# USBHeaders.net
KiCad netlist of a schematic drawn in Altium Designer
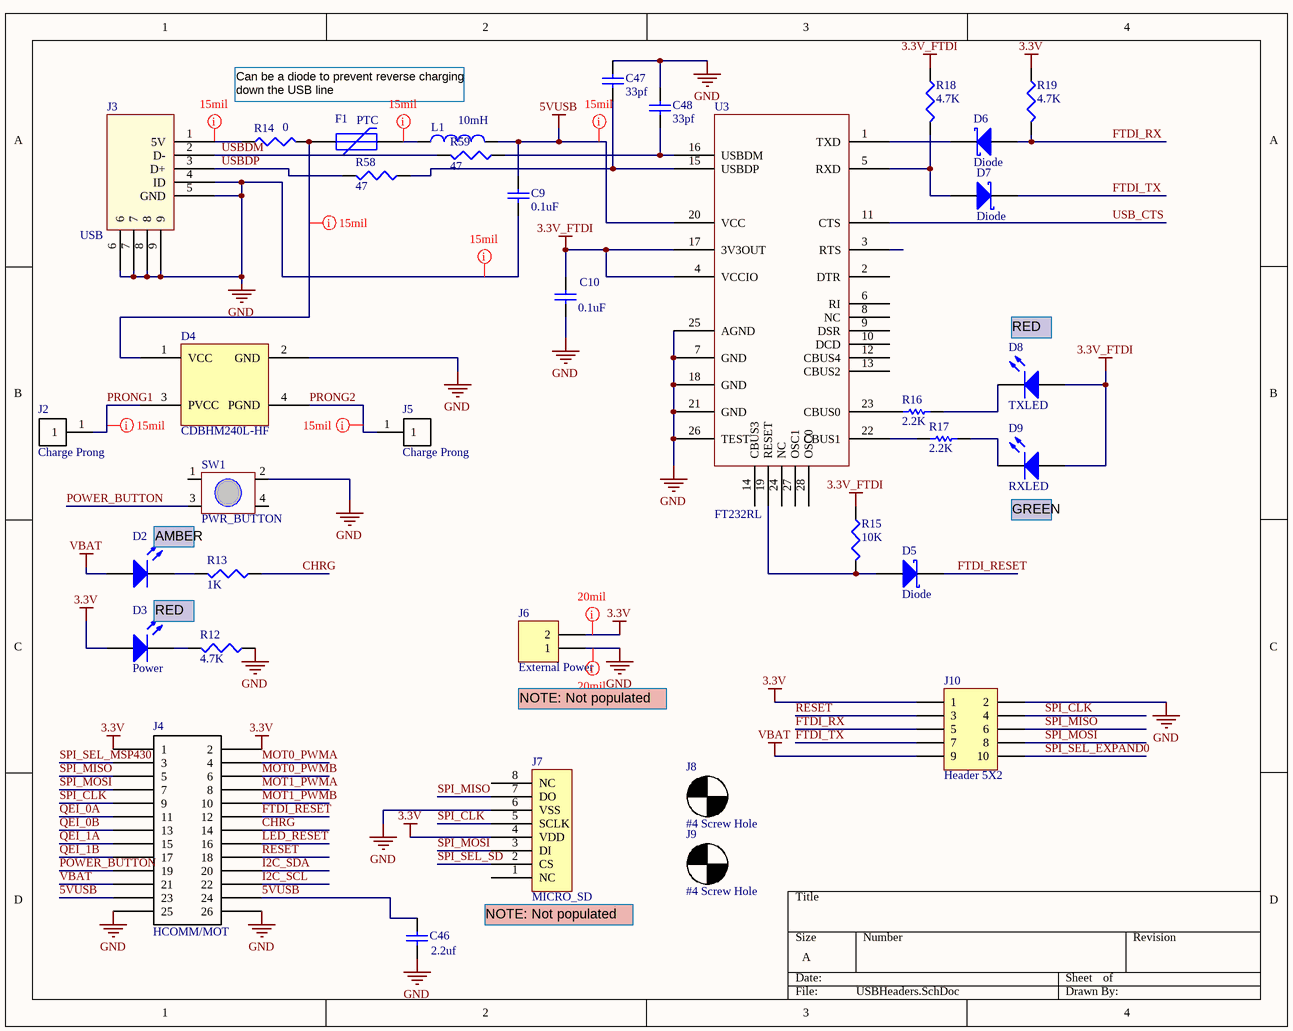
[diagram p0: USBHeaders.SchDoc]

(export (version "E")
  (design (tool "Eeschema 10.0.6"))
  (components
    (comp (ref "C9")
      (value "0.1uF")
      (footprint "CAPC1005L")
      (description "Capacitor")
      (fields
        (field (name "PART NUMBER") "C1005X5R1A104M050BA")
        (field (name "MANUFACTURER") "TDK")
        (field (name "PUBLISHER") "Altium Limited")
      )
      (libsource (lib "Miscellaneous Devices") (part "Cap"))
    )
    (comp (ref "C10")
      (value "0.1uF")
      (footprint "CAPC1005L")
      (description "Capacitor")
      (fields
        (field (name "PART NUMBER") "C1005X5R1A104M050BA")
        (field (name "MANUFACTURER") "TDK")
        (field (name "PUBLISHER") "Altium Limited")
      )
      (libsource (lib "Miscellaneous Devices") (part "Cap"))
    )
    (comp (ref "C46")
      (value "2.2uf")
      (footprint "J1-0603")
      (description "Capacitor (Semiconductor SIM Model)")
      (fields
        (field (name "PART NUMBER") "JMK107F225ZA-T")
        (field (name "MANUFACTURER") "Taiyo Yuden")
        (field (name "PUBLISHER") "Altium Limited")
      )
      (libsource (lib "Miscellaneous Devices") (part "Cap Semi"))
    )
    (comp (ref "C47")
      (value "33pf")
      (footprint "CAPC1005L")
      (description "Capacitor (Semiconductor SIM Model)")
      (fields
        (field (name "PART NUMBER") "GRM1555C1H330JA01D")
        (field (name "MANUFACTURER") "Murata")
        (field (name "PUBLISHER") "Altium Limited")
      )
      (libsource (lib "Miscellaneous Devices") (part "Cap Semi"))
    )
    (comp (ref "C48")
      (value "33pf")
      (footprint "CAPC1005L")
      (description "Capacitor (Semiconductor SIM Model)")
      (fields
        (field (name "PART NUMBER") "GRM1555C1H330JA01D")
        (field (name "MANUFACTURER") "Murata")
        (field (name "PUBLISHER") "Altium Limited")
      )
      (libsource (lib "Miscellaneous Devices") (part "Cap Semi"))
    )
    (comp (ref "D2")
      (value "Charge")
      (footprint "SurfaceMount(603)")
      (description "Typical RED, GREEN, YELLOW, AMBER GaAs LED")
      (fields
        (field (name "PART NUMBER") "LTST-C190AKT")
        (field (name "MANUFACTURER") "Lite-On")
        (field (name "PUBLISHER") "Altium Limited")
      )
      (libsource (lib "") (part "LED2_1"))
    )
    (comp (ref "D3")
      (value "Power")
      (footprint "SurfaceMount(603)")
      (fields (field (name "PART NUMBER") "LS Q976-NR-1") (field (name "MANUFACTURER") "Osram"))
      (libsource (lib "mrone") (part "LED"))
    )
    (comp (ref "D4")
      (value "CDBHM240L-HF")
      (footprint "DIODEARRAY_2AMPS")
      (fields
        (field (name "MPN") "CDBHM240L-HF")
        (field (name "PART NUMBER") "CDBHM240L - HF")
        (field (name "MANUFACTURER") "Comchip Technology")
      )
      (libsource (lib "mrone") (part "DiodeArray2Amps"))
    )
    (comp (ref "D5")
      (value "Diode")
      (footprint "SurfaceMount(603)")
      (fields (field (name "PART NUMBER") "CD0603-B00340") (field (name "MANUFACTURER") "Bourns"))
      (libsource (lib "mrone") (part "SchottkeyDiode"))
    )
    (comp (ref "D6")
      (value "Diode")
      (footprint "SurfaceMount(603)")
      (fields (field (name "PART NUMBER") "CD0603-B00340") (field (name "MANUFACTURER") "Bourns"))
      (libsource (lib "mrone") (part "SchottkeyDiode"))
    )
    (comp (ref "D7")
      (value "Diode")
      (footprint "SurfaceMount(603)")
      (fields (field (name "PART NUMBER") "CD0603-B00340") (field (name "MANUFACTURER") "Bourns"))
      (libsource (lib "mrone") (part "SchottkeyDiode"))
    )
    (comp (ref "D8")
      (value "TXLED")
      (footprint "SurfaceMount(603)")
      (description "Typical RED, GREEN, YELLOW, AMBER GaAs LED")
      (fields
        (field (name "PART NUMBER") "LS Q976-NR-1")
        (field (name "MANUFACTURER") "Osram")
        (field (name "PUBLISHER") "Altium Limited")
      )
      (libsource (lib "Miscellaneous Devices") (part "LED2"))
    )
    (comp (ref "D9")
      (value "RXLED")
      (footprint "SurfaceMount(603)")
      (description "Typical RED, GREEN, YELLOW, AMBER GaAs LED")
      (fields
        (field (name "PART NUMBER") "LTST-C191GKT")
        (field (name "MANUFACTURER") "Lite-On")
        (field (name "PUBLISHER") "Altium Limited")
      )
      (libsource (lib "Miscellaneous Devices") (part "LED2"))
    )
    (comp (ref "F1")
      (value "PTC")
      (footprint "ERJ8G-1206")
      (description "Fuse")
      (fields
        (field (name "PART NUMBER") "MF-NSMF200-2")
        (field (name "MANUFACTURER") "Bourns")
        (field (name "PUBLISHER") "Altium Limited")
      )
      (libsource (lib "mrone") (part "PTC_FUSE"))
    )
    (comp (ref "J2")
      (value "Charge Prong")
      (footprint "CHARGING_PRONG")
      (description "Charging Prong Hole with Plating")
      (libsource (lib "mrone") (part "CHARGE_PRONG"))
    )
    (comp (ref "J3")
      (value "USB")
      (footprint "USB Minib (thru-hole)")
      (fields (field (name "PART NUMBER") "51387-0578") (field (name "MANUFACTURER") "Molex"))
      (libsource (lib "mrone") (part "USB-ConnTH"))
    )
    (comp (ref "J4")
      (value "HCOMM/MOT")
      (footprint "HeaderSM 13x2")
      (description "Header, 2X20, 50mil, IDC")
      (fields (field (name "PART NUMBER") "SHF-113-01-L-D-SM-LC") (field (name "MANUFACTURER") "Samtec"))
      (libsource (lib "mrone") (part "HCOMM/HMOT"))
    )
    (comp (ref "J5")
      (value "Charge Prong")
      (footprint "CHARGING_PRONG")
      (description "Charging Prong Hole with Plating")
      (libsource (lib "mrone") (part "CHARGE_PRONG"))
    )
    (comp (ref "J6")
      (value "External Power")
      (footprint "HDR1X2")
      (description "Header, 2-Pin")
      (fields (field (name "PUBLISHER") "Altium Limited"))
      (libsource (lib "Miscellaneous Connectors") (part "Header 2"))
    )
    (comp (ref "J7")
      (value "MICRO_SD")
      (footprint "MICRO_SD")
      (fields (field (name "PART NUMBER") "101-00303-68") (field (name "MANUFACTURER") "Amphenol"))
      (libsource (lib "mrone") (part "MICRO_SD"))
    )
    (comp (ref "J8")
      (value "#4 Screw Hole")
      (footprint "#4_Screw_Hole")
      (description "A mechanical hole for mounting the board")
      (libsource (lib "mrone") (part "Mechanical_Hole"))
    )
    (comp (ref "J9")
      (value "#4 Screw Hole")
      (footprint "#4_Screw_Hole")
      (description "A mechanical hole for mounting the board")
      (libsource (lib "mrone") (part "Mechanical_Hole"))
    )
    (comp (ref "J10")
      (value "Header 5X2")
      (footprint "HDR2X5")
      (description "Header, 5-Pin, Dual row")
      (fields
        (field (name "PART NUMBER") "802-10-012-10-002101")
        (field (name "MANUFACTURER") "Preci-Dip")
        (field (name "PUBLISHER") "Altium Limited")
      )
      (libsource (lib "mrone") (part "Header 5X2"))
    )
    (comp (ref "L1")
      (value "10mH")
      (footprint "INDC2012L")
      (description "Inductor")
      (fields
        (field (name "PART NUMBER") "MMZ2012R102A")
        (field (name "MANUFACTURER") "TDK")
        (field (name "PUBLISHER") "Altium Limited")
      )
      (libsource (lib "Miscellaneous Devices") (part "Inductor"))
    )
    (comp (ref "R12")
      (value "4.7K")
      (footprint "RESC1608L")
      (description "Resistor")
      (fields
        (field (name "PART NUMBER") "CR0603-JW-472GLF")
        (field (name "MANUFACTURER") "Bourns")
        (field (name "PUBLISHER") "Altium Limited")
      )
      (libsource (lib "Miscellaneous Devices") (part "Res3"))
    )
    (comp (ref "R13")
      (value "1K")
      (footprint "RESC1608L")
      (description "Resistor")
      (fields
        (field (name "PART NUMBER") "SR03-1001")
        (field (name "MANUFACTURER") "Vishay")
        (field (name "PUBLISHER") "Altium Limited")
      )
      (libsource (lib "Miscellaneous Devices") (part "Res3"))
    )
    (comp (ref "R14")
      (value "0")
      (footprint "RESC1608L")
      (description "Resistor")
      (fields
        (field (name "PART NUMBER") "RMCF 1/16S 0 R")
        (field (name "MANUFACTURER") "Stackpole")
        (field (name "PUBLISHER") "Altium Limited")
      )
      (libsource (lib "Miscellaneous Devices") (part "Res3"))
    )
    (comp (ref "R15")
      (value "10K")
      (footprint "RESC1608L")
      (description "Resistor")
      (fields
        (field (name "PART NUMBER") "SR03-1002")
        (field (name "MANUFACTURER") "Vishay")
        (field (name "PUBLISHER") "Altium Limited")
      )
      (libsource (lib "Miscellaneous Devices") (part "Res3"))
    )
    (comp (ref "R16")
      (value "2.2K")
      (footprint "RESC1608L")
      (description "Resistor")
      (fields
        (field (name "PART NUMBER") "ERJ-3GEYJ-222V")
        (field (name "MANUFACTURER") "Panasonic")
        (field (name "PUBLISHER") "Altium Limited")
      )
      (libsource (lib "Miscellaneous Devices") (part "Res1"))
    )
    (comp (ref "R17")
      (value "2.2K")
      (footprint "RESC1608L")
      (description "Resistor")
      (fields
        (field (name "PART NUMBER") "ERJ-3GEYJ-222V")
        (field (name "MANUFACTURER") "Panasonic")
        (field (name "PUBLISHER") "Altium Limited")
      )
      (libsource (lib "Miscellaneous Devices") (part "Res1"))
    )
    (comp (ref "R18")
      (value "4.7K")
      (footprint "RESC1608L")
      (description "Resistor")
      (fields
        (field (name "PART NUMBER") "CR0603-JW-472GLF")
        (field (name "MANUFACTURER") "Bourns")
        (field (name "PUBLISHER") "Altium Limited")
      )
      (libsource (lib "Miscellaneous Devices") (part "Res3"))
    )
    (comp (ref "R19")
      (value "4.7K")
      (footprint "RESC1608L")
      (description "Resistor")
      (fields
        (field (name "PART NUMBER") "CR0603-JW-472GLF")
        (field (name "MANUFACTURER") "Bourns")
        (field (name "PUBLISHER") "Altium Limited")
      )
      (libsource (lib "Miscellaneous Devices") (part "Res3"))
    )
    (comp (ref "R58")
      (value "47")
      (footprint "RESC1608L")
      (description "Resistor")
      (fields
        (field (name "PART NUMBER") "ERJ-3GEYJ470V")
        (field (name "MANUFACTURER") "Panasonic")
        (field (name "PUBLISHER") "Altium Limited")
      )
      (libsource (lib "Miscellaneous Devices") (part "Res3"))
    )
    (comp (ref "R59")
      (value "47")
      (footprint "RESC1608L")
      (description "Resistor")
      (fields
        (field (name "PART NUMBER") "ERJ-3GEYJ470V")
        (field (name "MANUFACTURER") "Panasonic")
        (field (name "PUBLISHER") "Altium Limited")
      )
      (libsource (lib "Miscellaneous Devices") (part "Res3"))
    )
    (comp (ref "SW1")
      (value "PWR_BUTTON")
      (footprint "SwitchTall-TL330")
      (fields (field (name "PART NUMBER") "EVQ-P0N02B") (field (name "MANUFACTURER") "Panasonic"))
      (libsource (lib "mrone") (part "Switch-TL330"))
    )
    (comp (ref "U3")
      (value "FT232RL")
      (footprint "SSOP-28")
      (fields (field (name "MANUFACTURER") "FTDI"))
      (libsource (lib "mrone") (part "FT232RL"))
    )
  )
  (nets
    (net (code "2") (name "/CHRG") (class "Default")
      (node (ref "J4") (pin "14") (pinfunction "14_14") (pintype "passive"))
      (node (ref "R13") (pin "1") (pinfunction "1_1") (pintype "passive"))
    )
    (net (code "3") (name "/FTDI_RESET") (class "Default")
      (node (ref "D5") (pin "1") (pinfunction "K_1") (pintype "passive"))
      (node (ref "J4") (pin "12") (pinfunction "12_12") (pintype "passive"))
    )
    (net (code "4") (name "/FTDI_RX") (class "Default")
      (node (ref "D6") (pin "2") (pinfunction "A_2") (pintype "passive"))
      (node (ref "J10") (pin "5") (pinfunction "5_5") (pintype "passive"))
      (node (ref "R19") (pin "2") (pinfunction "2_2") (pintype "passive"))
    )
    (net (code "5") (name "/FTDI_TX") (class "Default")
      (node (ref "D7") (pin "1") (pinfunction "K_1") (pintype "passive"))
      (node (ref "J10") (pin "7") (pinfunction "7_7") (pintype "passive"))
    )
    (net (code "6") (name "/I2C_SCL") (class "Default")
      (node (ref "J4") (pin "22") (pinfunction "22_22") (pintype "passive"))
    )
    (net (code "7") (name "/I2C_SDA") (class "Default")
      (node (ref "J4") (pin "20") (pinfunction "20_20") (pintype "passive"))
    )
    (net (code "8") (name "/LED_RESET") (class "Default")
      (node (ref "J4") (pin "16") (pinfunction "16_16") (pintype "passive"))
    )
    (net (code "9") (name "/MOT0_PWMA") (class "Default")
      (node (ref "J4") (pin "4") (pinfunction "4_4") (pintype "passive"))
    )
    (net (code "10") (name "/MOT0_PWMB") (class "Default")
      (node (ref "J4") (pin "6") (pinfunction "6_6") (pintype "passive"))
    )
    (net (code "11") (name "/MOT1_PWMA") (class "Default")
      (node (ref "J4") (pin "8") (pinfunction "8_8") (pintype "passive"))
    )
    (net (code "12") (name "/MOT1_PWMB") (class "Default")
      (node (ref "J4") (pin "10") (pinfunction "10_10") (pintype "passive"))
    )
    (net (code "13") (name "/POWER_BUTTON") (class "Default")
      (node (ref "J4") (pin "19") (pinfunction "19_19") (pintype "passive"))
      (node (ref "SW1") (pin "3") (pinfunction "3_3") (pintype "passive"))
    )
    (net (code "14") (name "/PRONG1") (class "Default")
      (node (ref "D4") (pin "3") (pinfunction "PVCC_3") (pintype "passive"))
      (node (ref "J2") (pin "1") (pinfunction "1_1") (pintype "passive"))
    )
    (net (code "15") (name "/PRONG2") (class "Default")
      (node (ref "D4") (pin "4") (pinfunction "PGND_4") (pintype "passive"))
      (node (ref "J5") (pin "1") (pinfunction "1_1") (pintype "passive"))
    )
    (net (code "16") (name "/QEI_0A") (class "Default")
      (node (ref "J4") (pin "11") (pinfunction "11_11") (pintype "passive"))
    )
    (net (code "17") (name "/QEI_0B") (class "Default")
      (node (ref "J4") (pin "13") (pinfunction "13_13") (pintype "passive"))
    )
    (net (code "18") (name "/QEI_1A") (class "Default")
      (node (ref "J4") (pin "15") (pinfunction "15_15") (pintype "passive"))
    )
    (net (code "19") (name "/QEI_1B") (class "Default")
      (node (ref "J4") (pin "17") (pinfunction "17_17") (pintype "passive"))
    )
    (net (code "20") (name "/RESET") (class "Default")
      (node (ref "J10") (pin "3") (pinfunction "3_3") (pintype "passive"))
      (node (ref "J4") (pin "18") (pinfunction "18_18") (pintype "passive"))
    )
    (net (code "21") (name "/SPI_CLK") (class "Default")
      (node (ref "J10") (pin "4") (pinfunction "4_4") (pintype "passive"))
      (node (ref "J4") (pin "9") (pinfunction "9_9") (pintype "passive"))
      (node (ref "J7") (pin "5") (pinfunction "SCLK_5") (pintype "passive"))
    )
    (net (code "22") (name "/SPI_MISO") (class "Default")
      (node (ref "J10") (pin "6") (pinfunction "6_6") (pintype "passive"))
      (node (ref "J4") (pin "5") (pinfunction "5_5") (pintype "passive"))
      (node (ref "J7") (pin "7") (pinfunction "DO_7") (pintype "passive"))
    )
    (net (code "23") (name "/SPI_MOSI") (class "Default")
      (node (ref "J10") (pin "8") (pinfunction "8_8") (pintype "passive"))
      (node (ref "J4") (pin "7") (pinfunction "7_7") (pintype "passive"))
      (node (ref "J7") (pin "3") (pinfunction "DI_3") (pintype "passive"))
    )
    (net (code "24") (name "/SPI_SEL_EXPAND0") (class "Default")
      (node (ref "J10") (pin "10") (pinfunction "10_10") (pintype "passive"))
    )
    (net (code "25") (name "/SPI_SEL_MSP430") (class "Default")
      (node (ref "J4") (pin "3") (pinfunction "3_3") (pintype "passive"))
    )
    (net (code "26") (name "/SPI_SEL_SD") (class "Default")
      (node (ref "J7") (pin "2") (pinfunction "CS_2") (pintype "passive"))
    )
    (net (code "27") (name "/USBDM") (class "Default")
      (node (ref "J3") (pin "2") (pinfunction "D-_2") (pintype "passive"))
      (node (ref "R59") (pin "2") (pinfunction "2_2") (pintype "passive"))
    )
    (net (code "28") (name "/USBDP") (class "Default")
      (node (ref "J3") (pin "3") (pinfunction "D+_3") (pintype "passive"))
      (node (ref "R58") (pin "2") (pinfunction "2_2") (pintype "passive"))
    )
    (net (code "29") (name "/USB_CTS") (class "Default")
      (node (ref "U3") (pin "11") (pinfunction "CTS_11") (pintype "passive"))
    )
    (net (code "30") (name "3.3V") (class "Default")
      (node (ref "D3") (pin "1") (pinfunction "A_1") (pintype "passive"))
      (node (ref "J10") (pin "1") (pinfunction "1_1") (pintype "passive"))
      (node (ref "J4") (pin "1") (pinfunction "1_1") (pintype "passive"))
      (node (ref "J4") (pin "2") (pinfunction "2_2") (pintype "passive"))
      (node (ref "J6") (pin "2") (pinfunction "2_2") (pintype "passive"))
      (node (ref "J7") (pin "4") (pinfunction "VDD_4") (pintype "passive"))
      (node (ref "R19") (pin "1") (pinfunction "1_1") (pintype "passive"))
    )
    (net (code "31") (name "3.3V_FTDI") (class "Default")
      (node (ref "C10") (pin "2") (pinfunction "2_2") (pintype "passive"))
      (node (ref "D8") (pin "1") (pinfunction "A_1") (pintype "passive"))
      (node (ref "D9") (pin "1") (pinfunction "A_1") (pintype "passive"))
      (node (ref "R15") (pin "1") (pinfunction "1_1") (pintype "passive"))
      (node (ref "R18") (pin "1") (pinfunction "1_1") (pintype "passive"))
      (node (ref "U3") (pin "17") (pinfunction "3V3OUT_17") (pintype "passive"))
      (node (ref "U3") (pin "4") (pinfunction "VCCIO_4") (pintype "passive"))
    )
    (net (code "32") (name "5VUSB") (class "Default")
      (node (ref "C46") (pin "2") (pinfunction "2_2") (pintype "passive"))
      (node (ref "C9") (pin "2") (pinfunction "2_2") (pintype "passive"))
      (node (ref "J4") (pin "23") (pinfunction "23_23") (pintype "passive"))
      (node (ref "J4") (pin "24") (pinfunction "24_24") (pintype "passive"))
      (node (ref "L1") (pin "2") (pinfunction "2_2") (pintype "passive"))
      (node (ref "U3") (pin "20") (pinfunction "VCC_20") (pintype "passive"))
    )
    (net (code "33") (name "GND") (class "Default")
      (node (ref "C10") (pin "1") (pinfunction "1_1") (pintype "passive"))
      (node (ref "C46") (pin "1") (pinfunction "1_1") (pintype "passive"))
      (node (ref "C47") (pin "1") (pinfunction "1_1") (pintype "passive"))
      (node (ref "C48") (pin "1") (pinfunction "1_1") (pintype "passive"))
      (node (ref "C9") (pin "1") (pinfunction "1_1") (pintype "passive"))
      (node (ref "D4") (pin "2") (pinfunction "GND_2") (pintype "passive"))
      (node (ref "J10") (pin "2") (pinfunction "2_2") (pintype "passive"))
      (node (ref "J3") (pin "4") (pinfunction "ID_4") (pintype "passive"))
      (node (ref "J3") (pin "5") (pinfunction "GND_5") (pintype "passive"))
      (node (ref "J3") (pin "6") (pinfunction "6_6") (pintype "passive"))
      (node (ref "J3") (pin "7") (pinfunction "7_7") (pintype "passive"))
      (node (ref "J3") (pin "8") (pinfunction "8_8") (pintype "passive"))
      (node (ref "J3") (pin "9") (pinfunction "9_9") (pintype "passive"))
      (node (ref "J4") (pin "25") (pinfunction "25_25") (pintype "passive"))
      (node (ref "J4") (pin "26") (pinfunction "26_26") (pintype "passive"))
      (node (ref "J6") (pin "1") (pinfunction "1_1") (pintype "passive"))
      (node (ref "J7") (pin "6") (pinfunction "VSS_6") (pintype "passive"))
      (node (ref "R12") (pin "1") (pinfunction "1_1") (pintype "passive"))
      (node (ref "SW1") (pin "2") (pinfunction "2_2") (pintype "passive"))
      (node (ref "U3") (pin "18") (pinfunction "GND_18") (pintype "passive"))
      (node (ref "U3") (pin "21") (pinfunction "GND_21") (pintype "passive"))
      (node (ref "U3") (pin "25") (pinfunction "AGND_25") (pintype "passive"))
      (node (ref "U3") (pin "26") (pinfunction "TEST_26") (pintype "passive"))
      (node (ref "U3") (pin "7") (pinfunction "GND_7") (pintype "passive"))
    )
    (net (code "34") (name "Net-(D2-K)") (class "Default")
      (node (ref "D2") (pin "2") (pinfunction "K_2") (pintype "passive"))
      (node (ref "R13") (pin "2") (pinfunction "2_2") (pintype "passive"))
    )
    (net (code "35") (name "Net-(D3-K)") (class "Default")
      (node (ref "D3") (pin "2") (pinfunction "K_2") (pintype "passive"))
      (node (ref "R12") (pin "2") (pinfunction "2_2") (pintype "passive"))
    )
    (net (code "36") (name "Net-(D4-VCC)") (class "Default")
      (node (ref "D4") (pin "1") (pinfunction "VCC_1") (pintype "passive"))
      (node (ref "F1") (pin "2") (pinfunction "2_2") (pintype "passive"))
      (node (ref "R14") (pin "2") (pinfunction "2_2") (pintype "passive"))
    )
    (net (code "37") (name "Net-(D5-A)") (class "Default")
      (node (ref "D5") (pin "2") (pinfunction "A_2") (pintype "passive"))
      (node (ref "R15") (pin "2") (pinfunction "2_2") (pintype "passive"))
      (node (ref "U3") (pin "19") (pinfunction "RESET_19") (pintype "passive"))
    )
    (net (code "38") (name "Net-(D6-K)") (class "Default")
      (node (ref "D6") (pin "1") (pinfunction "K_1") (pintype "passive"))
      (node (ref "U3") (pin "1") (pinfunction "TXD_1") (pintype "passive"))
    )
    (net (code "39") (name "Net-(D7-A)") (class "Default")
      (node (ref "D7") (pin "2") (pinfunction "A_2") (pintype "passive"))
      (node (ref "R18") (pin "2") (pinfunction "2_2") (pintype "passive"))
      (node (ref "U3") (pin "5") (pinfunction "RXD_5") (pintype "passive"))
    )
    (net (code "40") (name "Net-(D8-K)") (class "Default")
      (node (ref "D8") (pin "2") (pinfunction "K_2") (pintype "passive"))
      (node (ref "R16") (pin "2") (pinfunction "2_2") (pintype "passive"))
    )
    (net (code "41") (name "Net-(D9-K)") (class "Default")
      (node (ref "D9") (pin "2") (pinfunction "K_2") (pintype "passive"))
      (node (ref "R17") (pin "2") (pinfunction "2_2") (pintype "passive"))
    )
    (net (code "42") (name "Net-(F1-Pad1)") (class "Default")
      (node (ref "F1") (pin "1") (pinfunction "1_1") (pintype "passive"))
      (node (ref "L1") (pin "1") (pinfunction "1_1") (pintype "passive"))
    )
    (net (code "43") (name "Net-(J3-5V)") (class "Default")
      (node (ref "J3") (pin "1") (pinfunction "5V_1") (pintype "passive"))
      (node (ref "R14") (pin "1") (pinfunction "1_1") (pintype "passive"))
    )
    (net (code "44") (name "Net-(U3-CBUS0)") (class "Default")
      (node (ref "R16") (pin "1") (pinfunction "1_1") (pintype "passive"))
      (node (ref "U3") (pin "23") (pinfunction "CBUS0_23") (pintype "passive"))
    )
    (net (code "45") (name "Net-(U3-CBUS1)") (class "Default")
      (node (ref "R17") (pin "1") (pinfunction "1_1") (pintype "passive"))
      (node (ref "U3") (pin "22") (pinfunction "CBUS1_22") (pintype "passive"))
    )
    (net (code "46") (name "Net-(U3-USBDM)") (class "Default")
      (node (ref "C48") (pin "2") (pinfunction "2_2") (pintype "passive"))
      (node (ref "R59") (pin "1") (pinfunction "1_1") (pintype "passive"))
      (node (ref "U3") (pin "16") (pinfunction "USBDM_16") (pintype "passive"))
    )
    (net (code "47") (name "Net-(U3-USBDP)") (class "Default")
      (node (ref "C47") (pin "2") (pinfunction "2_2") (pintype "passive"))
      (node (ref "R58") (pin "1") (pinfunction "1_1") (pintype "passive"))
      (node (ref "U3") (pin "15") (pinfunction "USBDP_15") (pintype "passive"))
    )
    (net (code "48") (name "VBAT") (class "Default")
      (node (ref "D2") (pin "1") (pinfunction "A_1") (pintype "passive"))
      (node (ref "J10") (pin "9") (pinfunction "9_9") (pintype "passive"))
      (node (ref "J4") (pin "21") (pinfunction "21_21") (pintype "passive"))
    )
    (net (code "49") (name "unconnected-(J7-NC-Pad1)") (class "Default")
      (node (ref "J7") (pin "1") (pinfunction "NC_1") (pintype "passive"))
    )
    (net (code "50") (name "unconnected-(J7-NC-Pad8)") (class "Default")
      (node (ref "J7") (pin "8") (pinfunction "NC_8") (pintype "passive"))
    )
    (net (code "51") (name "unconnected-(SW1-Pad1)") (class "Default")
      (node (ref "SW1") (pin "1") (pinfunction "1_1") (pintype "passive"))
    )
    (net (code "52") (name "unconnected-(SW1-Pad4)") (class "Default")
      (node (ref "SW1") (pin "4") (pinfunction "4_4") (pintype "passive"))
    )
    (net (code "53") (name "unconnected-(U3-CBUS2-Pad13)") (class "Default")
      (node (ref "U3") (pin "13") (pinfunction "CBUS2_13") (pintype "passive"))
    )
    (net (code "54") (name "unconnected-(U3-CBUS3-Pad14)") (class "Default")
      (node (ref "U3") (pin "14") (pinfunction "CBUS3_14") (pintype "passive"))
    )
    (net (code "55") (name "unconnected-(U3-CBUS4-Pad12)") (class "Default")
      (node (ref "U3") (pin "12") (pinfunction "CBUS4_12") (pintype "passive"))
    )
    (net (code "56") (name "unconnected-(U3-DCD-Pad10)") (class "Default")
      (node (ref "U3") (pin "10") (pinfunction "DCD_10") (pintype "passive"))
    )
    (net (code "57") (name "unconnected-(U3-DSR-Pad9)") (class "Default")
      (node (ref "U3") (pin "9") (pinfunction "DSR_9") (pintype "passive"))
    )
    (net (code "58") (name "unconnected-(U3-DTR-Pad2)") (class "Default")
      (node (ref "U3") (pin "2") (pinfunction "DTR_2") (pintype "passive"))
    )
    (net (code "59") (name "unconnected-(U3-NC-Pad8)") (class "Default")
      (node (ref "U3") (pin "8") (pinfunction "NC_8") (pintype "passive"))
    )
    (net (code "60") (name "unconnected-(U3-NC-Pad24)") (class "Default")
      (node (ref "U3") (pin "24") (pinfunction "NC_24") (pintype "passive"))
    )
    (net (code "61") (name "unconnected-(U3-OSC0-Pad28)") (class "Default")
      (node (ref "U3") (pin "28") (pinfunction "OSC0_28") (pintype "passive"))
    )
    (net (code "62") (name "unconnected-(U3-OSC1-Pad27)") (class "Default")
      (node (ref "U3") (pin "27") (pinfunction "OSC1_27") (pintype "passive"))
    )
    (net (code "63") (name "unconnected-(U3-RI-Pad6)") (class "Default")
      (node (ref "U3") (pin "6") (pinfunction "RI_6") (pintype "passive"))
    )
    (net (code "64") (name "unconnected-(U3-RTS-Pad3)") (class "Default")
      (node (ref "U3") (pin "3") (pinfunction "RTS_3") (pintype "passive"))
    )
  )
)
